# Good_morning.net
KiCad netlist of a schematic drawn in EAGLE
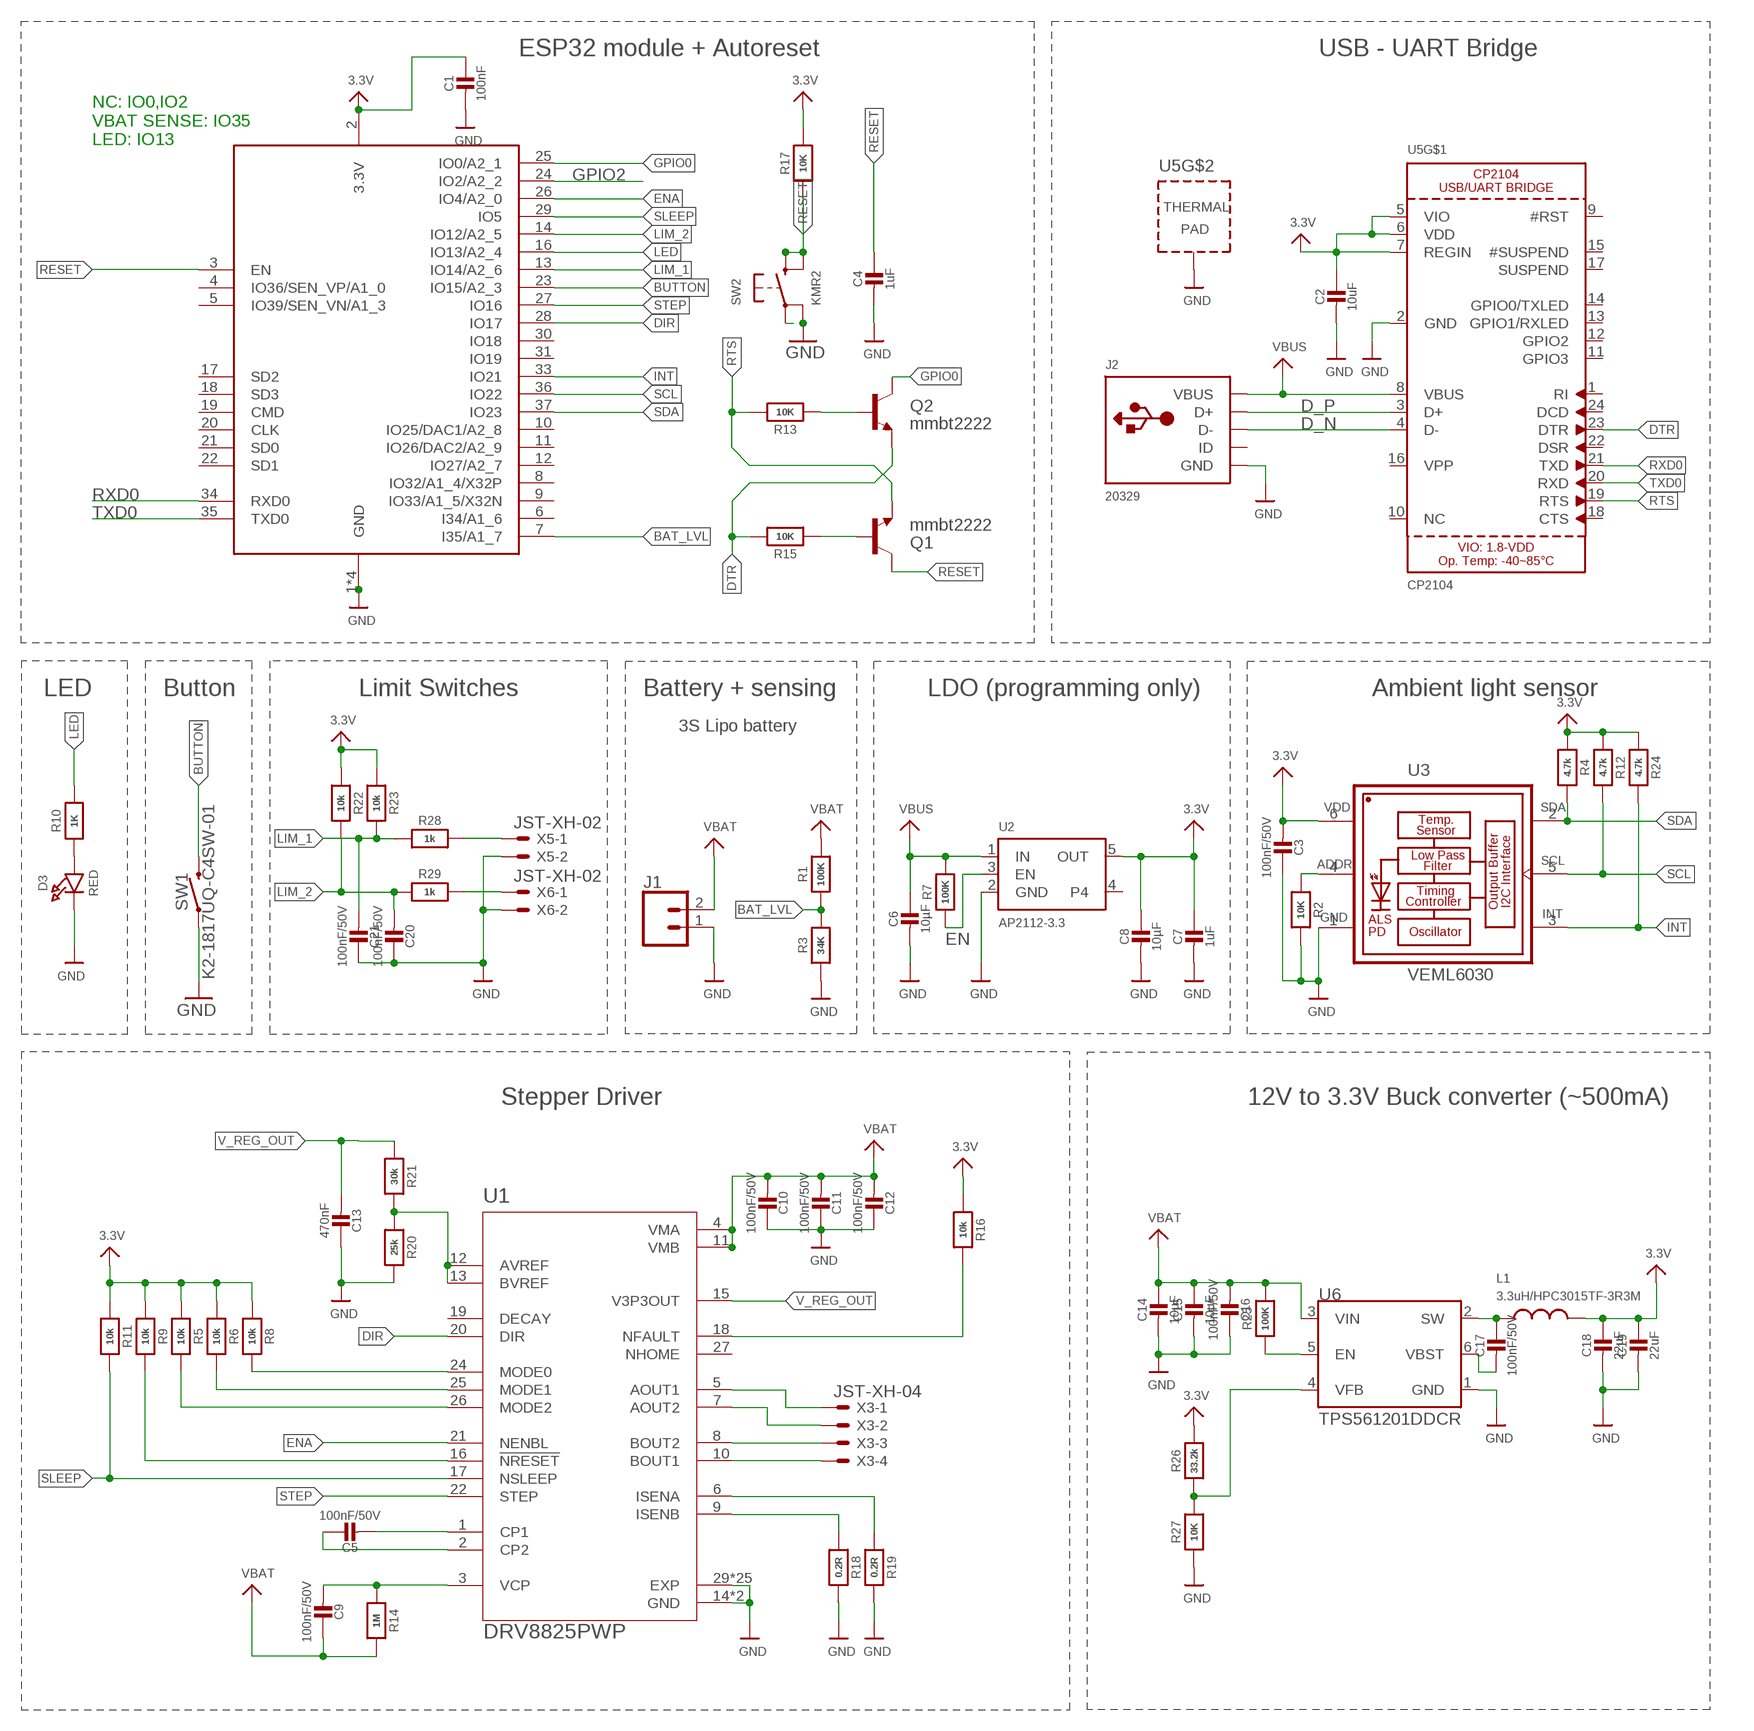
[diagram p0: schematic, sheet 1]

(export (version "E")
  (design (tool "Eeschema 10.0.6"))
  (components
    (comp (ref "C1")
      (value "100nF")
      (footprint "eagle-import:_0402")
      (libsource (lib "eagle-import") (part "CAP_CERAMIC_0402"))
    )
    (comp (ref "C2")
      (value "10uF")
      (footprint "eagle-import:_0402")
      (libsource (lib "eagle-import") (part "CAP_CERAMIC_0402"))
    )
    (comp (ref "C3")
      (value "100nF/50V")
      (footprint "eagle-import:_0402")
      (libsource (lib "eagle-import") (part "CAP_CERAMIC_0402"))
    )
    (comp (ref "C4")
      (value "1uF")
      (footprint "eagle-import:_0402")
      (libsource (lib "eagle-import") (part "CAP_CERAMIC_0402"))
    )
    (comp (ref "C5")
      (value "100nF/50V")
      (footprint "eagle-import:_0805")
      (libsource (lib "eagle-import") (part "CAP_CERAMIC_0805"))
    )
    (comp (ref "C6")
      (value "10µF")
      (footprint "eagle-import:_0402")
      (libsource (lib "eagle-import") (part "CAP_CERAMIC_0402"))
    )
    (comp (ref "C7")
      (value "1uF")
      (footprint "eagle-import:_0402")
      (libsource (lib "eagle-import") (part "CAP_CERAMIC_0402"))
    )
    (comp (ref "C8")
      (value "10µF")
      (footprint "eagle-import:_0402")
      (libsource (lib "eagle-import") (part "CAP_CERAMIC_0402"))
    )
    (comp (ref "C9")
      (value "100nF/50V")
      (footprint "eagle-import:_0805")
      (libsource (lib "eagle-import") (part "CAP_CERAMIC_0805"))
    )
    (comp (ref "C10")
      (value "100nF/50V")
      (footprint "eagle-import:_0805")
      (libsource (lib "eagle-import") (part "CAP_CERAMIC_0805"))
    )
    (comp (ref "C11")
      (value "100nF/50V")
      (footprint "eagle-import:_0805")
      (libsource (lib "eagle-import") (part "CAP_CERAMIC_0805"))
    )
    (comp (ref "C12")
      (value "100nF/50V")
      (footprint "eagle-import:_0805")
      (libsource (lib "eagle-import") (part "CAP_CERAMIC_0805"))
    )
    (comp (ref "C13")
      (value "470nF")
      (footprint "eagle-import:_0402")
      (libsource (lib "eagle-import") (part "CAP_CERAMIC_0402"))
    )
    (comp (ref "C14")
      (value "10µF")
      (footprint "eagle-import:_0402")
      (libsource (lib "eagle-import") (part "CAP_CERAMIC_0402"))
    )
    (comp (ref "C15")
      (value "10µF")
      (footprint "eagle-import:_0402")
      (libsource (lib "eagle-import") (part "CAP_CERAMIC_0402"))
    )
    (comp (ref "C16")
      (value "100nF/50V")
      (footprint "eagle-import:_0402")
      (libsource (lib "eagle-import") (part "CAP_CERAMIC_0402"))
    )
    (comp (ref "C17")
      (value "100nF/50V")
      (footprint "eagle-import:_0402")
      (libsource (lib "eagle-import") (part "CAP_CERAMIC_0402"))
    )
    (comp (ref "C18")
      (value "22uF")
      (footprint "eagle-import:_0402")
      (libsource (lib "eagle-import") (part "CAP_CERAMIC_0402"))
    )
    (comp (ref "C19")
      (value "22uF")
      (footprint "eagle-import:_0402")
      (libsource (lib "eagle-import") (part "CAP_CERAMIC_0402"))
    )
    (comp (ref "C20")
      (value "100nF/50V")
      (footprint "eagle-import:_0402")
      (libsource (lib "eagle-import") (part "CAP_CERAMIC_0402"))
    )
    (comp (ref "C21")
      (value "100nF/50V")
      (footprint "eagle-import:_0402")
      (libsource (lib "eagle-import") (part "CAP_CERAMIC_0402"))
    )
    (comp (ref "D3")
      (value "RED")
      (footprint "eagle-import:CHIPLED_0805_NOOUTLINE")
      (libsource (lib "eagle-import") (part "LED0805_NOOUTLINE"))
    )
    (comp (ref "J1")
      (value "CONN_023.5MM_LOCK")
      (footprint "eagle-import:SCREWTERMINAL-3.5MM-2_LOCK")
      (libsource (lib "eagle-import") (part "CONN_023.5MM_LOCK"))
    )
    (comp (ref "J2")
      (value "20329")
      (footprint "eagle-import:4UCONN_20329_V2")
      (libsource (lib "eagle-import") (part "USB_MICRO_20329_V2"))
    )
    (comp (ref "L1")
      (value "3.3uH/HPC3015TF-3R3M")
      (footprint "eagle-import:WPN4020H100MT")
      (libsource (lib "eagle-import") (part "WPN4020H100MT"))
    )
    (comp (ref "Q1")
      (value "mmbt2222")
      (footprint "eagle-import:SOT23-3")
      (libsource (lib "eagle-import") (part "TRANSISTOR_NPNSOT23-3"))
    )
    (comp (ref "Q2")
      (value "mmbt2222")
      (footprint "eagle-import:SOT23-3")
      (libsource (lib "eagle-import") (part "TRANSISTOR_NPNSOT23-3"))
    )
    (comp (ref "R1")
      (value "100K")
      (footprint "eagle-import:_0402")
      (libsource (lib "eagle-import") (part "RESISTOR_0402"))
    )
    (comp (ref "R2")
      (value "10K")
      (footprint "eagle-import:_0402")
      (libsource (lib "eagle-import") (part "RESISTOR_0402"))
    )
    (comp (ref "R3")
      (value "34K")
      (footprint "eagle-import:_0402")
      (libsource (lib "eagle-import") (part "RESISTOR_0402"))
    )
    (comp (ref "R4")
      (value "4.7k")
      (footprint "eagle-import:_0402")
      (libsource (lib "eagle-import") (part "RESISTOR_0402"))
    )
    (comp (ref "R5")
      (value "10k")
      (footprint "eagle-import:_0402")
      (libsource (lib "eagle-import") (part "RESISTOR_0402"))
    )
    (comp (ref "R6")
      (value "10k")
      (footprint "eagle-import:_0402")
      (libsource (lib "eagle-import") (part "RESISTOR_0402"))
    )
    (comp (ref "R7")
      (value "100K")
      (footprint "eagle-import:_0402")
      (libsource (lib "eagle-import") (part "RESISTOR_0402"))
    )
    (comp (ref "R8")
      (value "10k")
      (footprint "eagle-import:_0402")
      (libsource (lib "eagle-import") (part "RESISTOR_0402"))
    )
    (comp (ref "R9")
      (value "10k")
      (footprint "eagle-import:_0402")
      (libsource (lib "eagle-import") (part "RESISTOR_0402"))
    )
    (comp (ref "R10")
      (value "1K")
      (footprint "eagle-import:_0402")
      (libsource (lib "eagle-import") (part "RESISTOR_0402"))
    )
    (comp (ref "R11")
      (value "10k")
      (footprint "eagle-import:_0402")
      (libsource (lib "eagle-import") (part "RESISTOR_0402"))
    )
    (comp (ref "R12")
      (value "4.7k")
      (footprint "eagle-import:_0402")
      (libsource (lib "eagle-import") (part "RESISTOR_0402"))
    )
    (comp (ref "R13")
      (value "10K")
      (footprint "eagle-import:_0402")
      (libsource (lib "eagle-import") (part "RESISTOR_0402"))
    )
    (comp (ref "R14")
      (value "1M")
      (footprint "eagle-import:_0402")
      (libsource (lib "eagle-import") (part "RESISTOR_0402"))
    )
    (comp (ref "R15")
      (value "10K")
      (footprint "eagle-import:_0402")
      (libsource (lib "eagle-import") (part "RESISTOR_0402"))
    )
    (comp (ref "R16")
      (value "10k")
      (footprint "eagle-import:_0402")
      (libsource (lib "eagle-import") (part "RESISTOR_0402"))
    )
    (comp (ref "R17")
      (value "10K")
      (footprint "eagle-import:_0402")
      (libsource (lib "eagle-import") (part "RESISTOR_0402"))
    )
    (comp (ref "R18")
      (value "0.2R")
      (footprint "eagle-import:_1206")
      (libsource (lib "eagle-import") (part "RESISTOR_1206"))
    )
    (comp (ref "R19")
      (value "0.2R")
      (footprint "eagle-import:_1206")
      (libsource (lib "eagle-import") (part "RESISTOR_1206"))
    )
    (comp (ref "R20")
      (value "25k")
      (footprint "eagle-import:_0402")
      (libsource (lib "eagle-import") (part "RESISTOR_0402"))
    )
    (comp (ref "R21")
      (value "30k")
      (footprint "eagle-import:_0402")
      (libsource (lib "eagle-import") (part "RESISTOR_0402"))
    )
    (comp (ref "R22")
      (value "10k")
      (footprint "eagle-import:_0402")
      (libsource (lib "eagle-import") (part "RESISTOR_0402"))
    )
    (comp (ref "R23")
      (value "10k")
      (footprint "eagle-import:_0402")
      (libsource (lib "eagle-import") (part "RESISTOR_0402"))
    )
    (comp (ref "R24")
      (value "4.7k")
      (footprint "eagle-import:_0402")
      (libsource (lib "eagle-import") (part "RESISTOR_0402"))
    )
    (comp (ref "R25")
      (value "100K")
      (footprint "eagle-import:_0402")
      (libsource (lib "eagle-import") (part "RESISTOR_0402"))
    )
    (comp (ref "R26")
      (value "33.2k")
      (footprint "eagle-import:_0402")
      (libsource (lib "eagle-import") (part "RESISTOR_0402"))
    )
    (comp (ref "R27")
      (value "10K")
      (footprint "eagle-import:_0402")
      (libsource (lib "eagle-import") (part "RESISTOR_0402"))
    )
    (comp (ref "R28")
      (value "1k")
      (footprint "eagle-import:_0402")
      (libsource (lib "eagle-import") (part "RESISTOR_0402"))
    )
    (comp (ref "R29")
      (value "1k")
      (footprint "eagle-import:_0402")
      (libsource (lib "eagle-import") (part "RESISTOR_0402"))
    )
    (comp (ref "SW1")
      (value "K2-1817UQ-C4SW-01")
      (footprint "eagle-import:K2-1817UQ-C4SW-01")
      (libsource (lib "eagle-import") (part "K2-1817UQ-C4SW-01"))
    )
    (comp (ref "SW2")
      (value "KMR2")
      (footprint "eagle-import:BTN_KMR2_4.6X2.8")
      (libsource (lib "eagle-import") (part "SWITCH_TACT_SMT4.6X2.8"))
    )
    (comp (ref "U1")
      (value "DRV8825PWP")
      (footprint "eagle-import:SOP65P640X120-29N")
      (fields (field (name "MF") "Texas Instruments"))
      (libsource (lib "eagle-import") (part "DRV8825PWP"))
    )
    (comp (ref "U2")
      (value "AP2112-3.3")
      (footprint "eagle-import:SOT23-5")
      (libsource (lib "eagle-import") (part "VREG_SOT23-5"))
    )
    (comp (ref "U3")
      (value "VEML6030")
      (footprint "eagle-import:VISHAY_VEML6030_2X2X0.87")
      (fields (field (name "MF") "Vishay"))
      (libsource (lib "eagle-import") (part "VEML6030"))
    )
    (comp (ref "U4")
      (value "ESP32_WROOM32_SKINNY")
      (footprint "eagle-import:WROOM32_SKINNY")
      (libsource (lib "eagle-import") (part "ESP32_WROOM32_SKINNY"))
    )
    (comp (ref "U5")
      (value "CP2104")
      (footprint "eagle-import:QFN24_4MM_SMSC")
      (libsource (lib "eagle-import") (part "CP2104"))
    )
    (comp (ref "U6")
      (value "TPS561201DDCR")
      (footprint "eagle-import:SOT95P280X110-6N")
      (fields (field (name "MF") "Texas Instruments"))
      (libsource (lib "eagle-import") (part "TPS561201DDCR"))
    )
    (comp (ref "X3")
      (value "JST-XH-04")
      (footprint "eagle-import:JST-XH-04-PACKAGE-ROUND-PAD")
      (libsource (lib "eagle-import") (part "JST-XH-04-PIN-ROUND-PAD"))
    )
    (comp (ref "X5")
      (value "JST-XH-02")
      (footprint "eagle-import:JST-XH-02-PACKAGE-ROUND-PAD")
      (libsource (lib "eagle-import") (part "JST-XH-02-PIN-ROUND-PAD"))
    )
    (comp (ref "X6")
      (value "JST-XH-02")
      (footprint "eagle-import:JST-XH-02-PACKAGE-ROUND-PAD")
      (libsource (lib "eagle-import") (part "JST-XH-02-PIN-ROUND-PAD"))
    )
  )
  (nets
    (net (code "1") (name "/D_N") (class "Default")
      (node (ref "J2") (pin "D-") (pinfunction "D-_D-") (pintype "bidirectional"))
      (node (ref "U5") (pin "4") (pinfunction "D-_4") (pintype "bidirectional"))
    )
    (net (code "2") (name "/D_P") (class "Default")
      (node (ref "J2") (pin "D+") (pinfunction "D+_D+") (pintype "bidirectional"))
      (node (ref "U5") (pin "3") (pinfunction "D+_3") (pintype "bidirectional"))
    )
    (net (code "3") (name "/EN") (class "Default")
      (node (ref "R7") (pin "1") (pinfunction "1_1") (pintype "passive"))
      (node (ref "U2") (pin "3") (pinfunction "EN_3") (pintype "input"))
    )
    (net (code "4") (name "/GPIO2") (class "Default")
      (node (ref "U4") (pin "24") (pinfunction "IO2/A2_2_24") (pintype "bidirectional"))
    )
    (net (code "5") (name "3.3V") (class "Default")
      (node (ref "C1") (pin "1") (pinfunction "1_1") (pintype "passive"))
      (node (ref "C18") (pin "1") (pinfunction "1_1") (pintype "passive"))
      (node (ref "C19") (pin "1") (pinfunction "1_1") (pintype "passive"))
      (node (ref "C2") (pin "1") (pinfunction "1_1") (pintype "passive"))
      (node (ref "C3") (pin "2") (pinfunction "2_2") (pintype "passive"))
      (node (ref "C7") (pin "1") (pinfunction "1_1") (pintype "passive"))
      (node (ref "C8") (pin "1") (pinfunction "1_1") (pintype "passive"))
      (node (ref "L1") (pin "2") (pinfunction "2_2") (pintype "passive"))
      (node (ref "R11") (pin "1") (pinfunction "1_1") (pintype "passive"))
      (node (ref "R12") (pin "1") (pinfunction "1_1") (pintype "passive"))
      (node (ref "R16") (pin "1") (pinfunction "1_1") (pintype "passive"))
      (node (ref "R17") (pin "2") (pinfunction "2_2") (pintype "passive"))
      (node (ref "R22") (pin "1") (pinfunction "1_1") (pintype "passive"))
      (node (ref "R23") (pin "1") (pinfunction "1_1") (pintype "passive"))
      (node (ref "R24") (pin "1") (pinfunction "1_1") (pintype "passive"))
      (node (ref "R26") (pin "1") (pinfunction "1_1") (pintype "passive"))
      (node (ref "R4") (pin "1") (pinfunction "1_1") (pintype "passive"))
      (node (ref "R5") (pin "1") (pinfunction "1_1") (pintype "passive"))
      (node (ref "R6") (pin "1") (pinfunction "1_1") (pintype "passive"))
      (node (ref "R8") (pin "1") (pinfunction "1_1") (pintype "passive"))
      (node (ref "R9") (pin "1") (pinfunction "1_1") (pintype "passive"))
      (node (ref "U2") (pin "5") (pinfunction "OUT_5") (pintype "power_in"))
      (node (ref "U3") (pin "6") (pinfunction "VDD_6") (pintype "power_in"))
      (node (ref "U4") (pin "2") (pinfunction "3.3V_2") (pintype "passive"))
      (node (ref "U5") (pin "5") (pinfunction "VIO_5") (pintype "power_in"))
      (node (ref "U5") (pin "6") (pinfunction "VDD_6") (pintype "power_in"))
      (node (ref "U5") (pin "7") (pinfunction "REGIN_7") (pintype "power_in"))
    )
    (net (code "6") (name "BAT_LVL") (class "Default")
      (node (ref "R1") (pin "1") (pinfunction "1_1") (pintype "passive"))
      (node (ref "R3") (pin "2") (pinfunction "2_2") (pintype "passive"))
      (node (ref "U4") (pin "7") (pinfunction "I35/A1_7_7") (pintype "bidirectional"))
    )
    (net (code "7") (name "BUTTON") (class "Default")
      (node (ref "SW1") (pin "P$2") (pinfunction "2_P$2") (pintype "passive"))
      (node (ref "U4") (pin "23") (pinfunction "IO15/A2_3_23") (pintype "bidirectional"))
    )
    (net (code "8") (name "DIR") (class "Default")
      (node (ref "U1") (pin "20") (pinfunction "DIR_20") (pintype "input"))
      (node (ref "U4") (pin "28") (pinfunction "IO17_28") (pintype "bidirectional"))
    )
    (net (code "9") (name "DTR") (class "Default")
      (node (ref "Q2") (pin "2") (pinfunction "E_2") (pintype "passive"))
      (node (ref "R15") (pin "2") (pinfunction "2_2") (pintype "passive"))
      (node (ref "U5") (pin "23") (pinfunction "DTR_23") (pintype "output"))
    )
    (net (code "10") (name "ENA") (class "Default")
      (node (ref "U1") (pin "21") (pinfunction "NENBL_21") (pintype "input"))
      (node (ref "U4") (pin "26") (pinfunction "IO4/A2_0_26") (pintype "bidirectional"))
    )
    (net (code "11") (name "GND") (class "Default")
      (node (ref "C1") (pin "2") (pinfunction "2_2") (pintype "passive"))
      (node (ref "C10") (pin "1") (pinfunction "1_1") (pintype "passive"))
      (node (ref "C11") (pin "1") (pinfunction "1_1") (pintype "passive"))
      (node (ref "C12") (pin "1") (pinfunction "1_1") (pintype "passive"))
      (node (ref "C13") (pin "1") (pinfunction "1_1") (pintype "passive"))
      (node (ref "C14") (pin "2") (pinfunction "2_2") (pintype "passive"))
      (node (ref "C15") (pin "2") (pinfunction "2_2") (pintype "passive"))
      (node (ref "C16") (pin "1") (pinfunction "1_1") (pintype "passive"))
      (node (ref "C18") (pin "2") (pinfunction "2_2") (pintype "passive"))
      (node (ref "C19") (pin "2") (pinfunction "2_2") (pintype "passive"))
      (node (ref "C2") (pin "2") (pinfunction "2_2") (pintype "passive"))
      (node (ref "C20") (pin "1") (pinfunction "1_1") (pintype "passive"))
      (node (ref "C21") (pin "1") (pinfunction "1_1") (pintype "passive"))
      (node (ref "C3") (pin "1") (pinfunction "1_1") (pintype "passive"))
      (node (ref "C4") (pin "2") (pinfunction "2_2") (pintype "passive"))
      (node (ref "C6") (pin "2") (pinfunction "2_2") (pintype "passive"))
      (node (ref "C7") (pin "2") (pinfunction "2_2") (pintype "passive"))
      (node (ref "C8") (pin "2") (pinfunction "2_2") (pintype "passive"))
      (node (ref "D3") (pin "C") (pinfunction "C_C") (pintype "passive"))
      (node (ref "J1") (pin "1") (pinfunction "1_1") (pintype "passive"))
      (node (ref "J2") (pin "BASE@1") (pinfunction "GND_BASE@1") (pintype "power_in"))
      (node (ref "J2") (pin "BASE@2") (pinfunction "GND_BASE@2") (pintype "power_in"))
      (node (ref "J2") (pin "GND") (pinfunction "GND_GND") (pintype "power_in"))
      (node (ref "J2") (pin "SPRT@1") (pinfunction "GND_SPRT@1") (pintype "power_in"))
      (node (ref "J2") (pin "SPRT@2") (pinfunction "GND_SPRT@2") (pintype "power_in"))
      (node (ref "J2") (pin "SPRT@3") (pinfunction "GND_SPRT@3") (pintype "power_in"))
      (node (ref "J2") (pin "SPRT@4") (pinfunction "GND_SPRT@4") (pintype "power_in"))
      (node (ref "R18") (pin "2") (pinfunction "2_2") (pintype "passive"))
      (node (ref "R19") (pin "2") (pinfunction "2_2") (pintype "passive"))
      (node (ref "R2") (pin "2") (pinfunction "2_2") (pintype "passive"))
      (node (ref "R20") (pin "2") (pinfunction "2_2") (pintype "passive"))
      (node (ref "R27") (pin "1") (pinfunction "1_1") (pintype "passive"))
      (node (ref "R3") (pin "1") (pinfunction "1_1") (pintype "passive"))
      (node (ref "SW1") (pin "P$1") (pinfunction "1_P$1") (pintype "passive"))
      (node (ref "SW2") (pin "A'") (pinfunction "P1_A'") (pintype "passive"))
      (node (ref "U1") (pin "14") (pinfunction "GND_14") (pintype "power_in"))
      (node (ref "U1") (pin "28") (pinfunction "GND_28") (pintype "power_in"))
      (node (ref "U1") (pin "29") (pinfunction "EXP_29") (pintype "power_in"))
      (node (ref "U1") (pin "P1") (pinfunction "EXP_P1") (pintype "power_in"))
      (node (ref "U1") (pin "P10") (pinfunction "EXP_P10") (pintype "power_in"))
      (node (ref "U1") (pin "P11") (pinfunction "EXP_P11") (pintype "power_in"))
      (node (ref "U1") (pin "P12") (pinfunction "EXP_P12") (pintype "power_in"))
      (node (ref "U1") (pin "P13") (pinfunction "EXP_P13") (pintype "power_in"))
      (node (ref "U1") (pin "P14") (pinfunction "EXP_P14") (pintype "power_in"))
      (node (ref "U1") (pin "P15") (pinfunction "EXP_P15") (pintype "power_in"))
      (node (ref "U1") (pin "P16") (pinfunction "EXP_P16") (pintype "power_in"))
      (node (ref "U1") (pin "P17") (pinfunction "EXP_P17") (pintype "power_in"))
      (node (ref "U1") (pin "P18") (pinfunction "EXP_P18") (pintype "power_in"))
      (node (ref "U1") (pin "P19") (pinfunction "EXP_P19") (pintype "power_in"))
      (node (ref "U1") (pin "P2") (pinfunction "EXP_P2") (pintype "power_in"))
      (node (ref "U1") (pin "P20") (pinfunction "EXP_P20") (pintype "power_in"))
      (node (ref "U1") (pin "P21") (pinfunction "EXP_P21") (pintype "power_in"))
      (node (ref "U1") (pin "P22") (pinfunction "EXP_P22") (pintype "power_in"))
      (node (ref "U1") (pin "P23") (pinfunction "EXP_P23") (pintype "power_in"))
      (node (ref "U1") (pin "P24") (pinfunction "EXP_P24") (pintype "power_in"))
      (node (ref "U1") (pin "P3") (pinfunction "EXP_P3") (pintype "power_in"))
      (node (ref "U1") (pin "P4") (pinfunction "EXP_P4") (pintype "power_in"))
      (node (ref "U1") (pin "P5") (pinfunction "EXP_P5") (pintype "power_in"))
      (node (ref "U1") (pin "P6") (pinfunction "EXP_P6") (pintype "power_in"))
      (node (ref "U1") (pin "P7") (pinfunction "EXP_P7") (pintype "power_in"))
      (node (ref "U1") (pin "P8") (pinfunction "EXP_P8") (pintype "power_in"))
      (node (ref "U1") (pin "P9") (pinfunction "EXP_P9") (pintype "power_in"))
      (node (ref "U2") (pin "2") (pinfunction "GND_2") (pintype "power_in"))
      (node (ref "U3") (pin "1") (pinfunction "GND_1") (pintype "power_in"))
      (node (ref "U4") (pin "1") (pinfunction "GND_1") (pintype "passive"))
      (node (ref "U4") (pin "15") (pinfunction "GND_15") (pintype "passive"))
      (node (ref "U4") (pin "38") (pinfunction "GND_38") (pintype "passive"))
      (node (ref "U4") (pin "P$1") (pinfunction "GND_P$1") (pintype "passive"))
      (node (ref "U5") (pin "2") (pinfunction "GND_2") (pintype "power_in"))
      (node (ref "U5") (pin "THERM") (pinfunction "TP_THERM") (pintype "power_in"))
      (node (ref "U6") (pin "1") (pinfunction "GND_1") (pintype "power_in"))
      (node (ref "X5") (pin "2") (pinfunction "S_2") (pintype "passive"))
      (node (ref "X6") (pin "2") (pinfunction "S_2") (pintype "passive"))
    )
    (net (code "12") (name "GPIO0") (class "Default")
      (node (ref "Q2") (pin "3") (pinfunction "C_3") (pintype "passive"))
      (node (ref "U4") (pin "25") (pinfunction "IO0/A2_1_25") (pintype "bidirectional"))
    )
    (net (code "13") (name "INT") (class "Default")
      (node (ref "R24") (pin "2") (pinfunction "2_2") (pintype "passive"))
      (node (ref "U3") (pin "3") (pinfunction "INT_3") (pintype "output"))
      (node (ref "U4") (pin "33") (pinfunction "IO21_33") (pintype "bidirectional"))
    )
    (net (code "14") (name "LED") (class "Default")
      (node (ref "R10") (pin "1") (pinfunction "1_1") (pintype "passive"))
      (node (ref "U4") (pin "16") (pinfunction "IO13/A2_4_16") (pintype "bidirectional"))
    )
    (net (code "15") (name "LIM_1") (class "Default")
      (node (ref "C21") (pin "2") (pinfunction "2_2") (pintype "passive"))
      (node (ref "R23") (pin "2") (pinfunction "2_2") (pintype "passive"))
      (node (ref "R28") (pin "1") (pinfunction "1_1") (pintype "passive"))
      (node (ref "U4") (pin "13") (pinfunction "IO14/A2_6_13") (pintype "bidirectional"))
    )
    (net (code "16") (name "LIM_2") (class "Default")
      (node (ref "C20") (pin "2") (pinfunction "2_2") (pintype "passive"))
      (node (ref "R22") (pin "2") (pinfunction "2_2") (pintype "passive"))
      (node (ref "R29") (pin "1") (pinfunction "1_1") (pintype "passive"))
      (node (ref "U4") (pin "14") (pinfunction "IO12/A2_5_14") (pintype "bidirectional"))
    )
    (net (code "17") (name "Net-(D3-PadA)") (class "Default")
      (node (ref "D3") (pin "A") (pinfunction "A_A") (pintype "passive"))
      (node (ref "R10") (pin "2") (pinfunction "2_2") (pintype "passive"))
    )
    (net (code "18") (name "Net-(Q1-B)") (class "Default")
      (node (ref "Q1") (pin "1") (pinfunction "B_1") (pintype "passive"))
      (node (ref "R15") (pin "1") (pinfunction "1_1") (pintype "passive"))
    )
    (net (code "19") (name "Net-(Q2-B)") (class "Default")
      (node (ref "Q2") (pin "1") (pinfunction "B_1") (pintype "passive"))
      (node (ref "R13") (pin "1") (pinfunction "1_1") (pintype "passive"))
    )
    (net (code "20") (name "Net-(U1-AOUT1)") (class "Default")
      (node (ref "U1") (pin "5") (pinfunction "AOUT1_5") (pintype "output"))
      (node (ref "X3") (pin "1") (pinfunction "S_1") (pintype "passive"))
    )
    (net (code "21") (name "Net-(U1-AOUT2)") (class "Default")
      (node (ref "U1") (pin "7") (pinfunction "AOUT2_7") (pintype "output"))
      (node (ref "X3") (pin "2") (pinfunction "S_2") (pintype "passive"))
    )
    (net (code "22") (name "Net-(U1-AVREF)") (class "Default")
      (node (ref "R20") (pin "1") (pinfunction "1_1") (pintype "passive"))
      (node (ref "R21") (pin "2") (pinfunction "2_2") (pintype "passive"))
      (node (ref "U1") (pin "12") (pinfunction "AVREF_12") (pintype "input"))
      (node (ref "U1") (pin "13") (pinfunction "BVREF_13") (pintype "input"))
    )
    (net (code "23") (name "Net-(U1-BOUT1)") (class "Default")
      (node (ref "U1") (pin "10") (pinfunction "BOUT1_10") (pintype "output"))
      (node (ref "X3") (pin "4") (pinfunction "S_4") (pintype "passive"))
    )
    (net (code "24") (name "Net-(U1-BOUT2)") (class "Default")
      (node (ref "U1") (pin "8") (pinfunction "BOUT2_8") (pintype "output"))
      (node (ref "X3") (pin "3") (pinfunction "S_3") (pintype "passive"))
    )
    (net (code "25") (name "Net-(U1-CP1)") (class "Default")
      (node (ref "C5") (pin "2") (pinfunction "2_2") (pintype "passive"))
      (node (ref "U1") (pin "1") (pinfunction "CP1_1") (pintype "bidirectional"))
    )
    (net (code "26") (name "Net-(U1-CP2)") (class "Default")
      (node (ref "C5") (pin "1") (pinfunction "1_1") (pintype "passive"))
      (node (ref "U1") (pin "2") (pinfunction "CP2_2") (pintype "bidirectional"))
    )
    (net (code "27") (name "Net-(U1-ISENA)") (class "Default")
      (node (ref "R19") (pin "1") (pinfunction "1_1") (pintype "passive"))
      (node (ref "U1") (pin "6") (pinfunction "ISENA_6") (pintype "bidirectional"))
    )
    (net (code "28") (name "Net-(U1-ISENB)") (class "Default")
      (node (ref "R18") (pin "1") (pinfunction "1_1") (pintype "passive"))
      (node (ref "U1") (pin "9") (pinfunction "ISENB_9") (pintype "bidirectional"))
    )
    (net (code "29") (name "Net-(U1-MODE0)") (class "Default")
      (node (ref "R8") (pin "2") (pinfunction "2_2") (pintype "passive"))
      (node (ref "U1") (pin "24") (pinfunction "MODE0_24") (pintype "input"))
    )
    (net (code "30") (name "Net-(U1-MODE1)") (class "Default")
      (node (ref "R6") (pin "2") (pinfunction "2_2") (pintype "passive"))
      (node (ref "U1") (pin "25") (pinfunction "MODE1_25") (pintype "input"))
    )
    (net (code "31") (name "Net-(U1-MODE2)") (class "Default")
      (node (ref "R5") (pin "2") (pinfunction "2_2") (pintype "passive"))
      (node (ref "U1") (pin "26") (pinfunction "MODE2_26") (pintype "input"))
    )
    (net (code "32") (name "Net-(U1-NFAULT)") (class "Default")
      (node (ref "R16") (pin "2") (pinfunction "2_2") (pintype "passive"))
      (node (ref "U1") (pin "18") (pinfunction "NFAULT_18") (pintype "output"))
    )
    (net (code "33") (name "Net-(U1-VCP)") (class "Default")
      (node (ref "C9") (pin "2") (pinfunction "2_2") (pintype "passive"))
      (node (ref "R14") (pin "1") (pinfunction "1_1") (pintype "passive"))
      (node (ref "U1") (pin "3") (pinfunction "VCP_3") (pintype "bidirectional"))
    )
    (net (code "34") (name "Net-(U1-~{NRESET})") (class "Default")
      (node (ref "R9") (pin "2") (pinfunction "2_2") (pintype "passive"))
      (node (ref "U1") (pin "16") (pinfunction "~{NRESET}_16") (pintype "input"))
    )
    (net (code "35") (name "Net-(U3-ADDR)") (class "Default")
      (node (ref "R2") (pin "1") (pinfunction "1_1") (pintype "passive"))
      (node (ref "U3") (pin "4") (pinfunction "ADDR_4") (pintype "bidirectional"))
    )
    (net (code "36") (name "Net-(U6-EN)") (class "Default")
      (node (ref "R25") (pin "1") (pinfunction "1_1") (pintype "passive"))
      (node (ref "U6") (pin "5") (pinfunction "EN_5") (pintype "input"))
    )
    (net (code "37") (name "Net-(U6-SW)") (class "Default")
      (node (ref "C17") (pin "1") (pinfunction "1_1") (pintype "passive"))
      (node (ref "L1") (pin "1") (pinfunction "1_1") (pintype "passive"))
      (node (ref "U6") (pin "2") (pinfunction "SW_2") (pintype "output"))
    )
    (net (code "38") (name "Net-(U6-VBST)") (class "Default")
      (node (ref "C17") (pin "2") (pinfunction "2_2") (pintype "passive"))
      (node (ref "U6") (pin "6") (pinfunction "VBST_6") (pintype "passive"))
    )
    (net (code "39") (name "Net-(U6-VFB)") (class "Default")
      (node (ref "R26") (pin "2") (pinfunction "2_2") (pintype "passive"))
      (node (ref "R27") (pin "2") (pinfunction "2_2") (pintype "passive"))
      (node (ref "U6") (pin "4") (pinfunction "VFB_4") (pintype "input"))
    )
    (net (code "40") (name "Net-(X5A-S)") (class "Default")
      (node (ref "R28") (pin "2") (pinfunction "2_2") (pintype "passive"))
      (node (ref "X5") (pin "1") (pinfunction "S_1") (pintype "passive"))
    )
    (net (code "41") (name "Net-(X6A-S)") (class "Default")
      (node (ref "R29") (pin "2") (pinfunction "2_2") (pintype "passive"))
      (node (ref "X6") (pin "1") (pinfunction "S_1") (pintype "passive"))
    )
    (net (code "42") (name "RESET") (class "Default")
      (node (ref "C4") (pin "1") (pinfunction "1_1") (pintype "passive"))
      (node (ref "Q1") (pin "3") (pinfunction "C_3") (pintype "passive"))
      (node (ref "R17") (pin "1") (pinfunction "1_1") (pintype "passive"))
      (node (ref "SW2") (pin "B") (pinfunction "S_B") (pintype "passive"))
      (node (ref "SW2") (pin "B'") (pinfunction "S1_B'") (pintype "passive"))
      (node (ref "U4") (pin "3") (pinfunction "EN_3") (pintype "input"))
    )
    (net (code "43") (name "RTS") (class "Default")
      (node (ref "Q1") (pin "2") (pinfunction "E_2") (pintype "passive"))
      (node (ref "R13") (pin "2") (pinfunction "2_2") (pintype "passive"))
      (node (ref "U5") (pin "19") (pinfunction "RTS_19") (pintype "output"))
    )
    (net (code "44") (name "RXD0") (class "Default")
      (node (ref "U4") (pin "34") (pinfunction "RXD0_34") (pintype "input"))
      (node (ref "U5") (pin "21") (pinfunction "TXD_21") (pintype "output"))
    )
    (net (code "45") (name "SCL") (class "Default")
      (node (ref "R12") (pin "2") (pinfunction "2_2") (pintype "passive"))
      (node (ref "U3") (pin "5") (pinfunction "SCL_5") (pintype "input"))
      (node (ref "U4") (pin "36") (pinfunction "IO22_36") (pintype "bidirectional"))
    )
    (net (code "46") (name "SDA") (class "Default")
      (node (ref "R4") (pin "2") (pinfunction "2_2") (pintype "passive"))
      (node (ref "U3") (pin "2") (pinfunction "SDA_2") (pintype "bidirectional"))
      (node (ref "U4") (pin "37") (pinfunction "IO23_37") (pintype "bidirectional"))
    )
    (net (code "47") (name "SLEEP") (class "Default")
      (node (ref "R11") (pin "2") (pinfunction "2_2") (pintype "passive"))
      (node (ref "U1") (pin "17") (pinfunction "NSLEEP_17") (pintype "input"))
      (node (ref "U4") (pin "29") (pinfunction "IO5_29") (pintype "bidirectional"))
    )
    (net (code "48") (name "STEP") (class "Default")
      (node (ref "U1") (pin "22") (pinfunction "STEP_22") (pintype "input"))
      (node (ref "U4") (pin "27") (pinfunction "IO16_27") (pintype "bidirectional"))
    )
    (net (code "49") (name "TXD0") (class "Default")
      (node (ref "U4") (pin "35") (pinfunction "TXD0_35") (pintype "output"))
      (node (ref "U5") (pin "20") (pinfunction "RXD_20") (pintype "input"))
    )
    (net (code "50") (name "VBAT") (class "Default")
      (node (ref "C10") (pin "2") (pinfunction "2_2") (pintype "passive"))
      (node (ref "C11") (pin "2") (pinfunction "2_2") (pintype "passive"))
      (node (ref "C12") (pin "2") (pinfunction "2_2") (pintype "passive"))
      (node (ref "C14") (pin "1") (pinfunction "1_1") (pintype "passive"))
      (node (ref "C15") (pin "1") (pinfunction "1_1") (pintype "passive"))
      (node (ref "C16") (pin "2") (pinfunction "2_2") (pintype "passive"))
      (node (ref "C9") (pin "1") (pinfunction "1_1") (pintype "passive"))
      (node (ref "J1") (pin "2") (pinfunction "2_2") (pintype "passive"))
      (node (ref "R1") (pin "2") (pinfunction "2_2") (pintype "passive"))
      (node (ref "R14") (pin "2") (pinfunction "2_2") (pintype "passive"))
      (node (ref "R25") (pin "2") (pinfunction "2_2") (pintype "passive"))
      (node (ref "U1") (pin "11") (pinfunction "VMB_11") (pintype "power_in"))
      (node (ref "U1") (pin "4") (pinfunction "VMA_4") (pintype "power_in"))
      (node (ref "U6") (pin "3") (pinfunction "VIN_3") (pintype "input"))
    )
    (net (code "51") (name "VBUS") (class "Default")
      (node (ref "C6") (pin "1") (pinfunction "1_1") (pintype "passive"))
      (node (ref "J2") (pin "VBUS") (pinfunction "VBUS_VBUS") (pintype "power_in"))
      (node (ref "R7") (pin "2") (pinfunction "2_2") (pintype "passive"))
      (node (ref "U2") (pin "1") (pinfunction "IN_1") (pintype "power_in"))
      (node (ref "U5") (pin "8") (pinfunction "VBUS_8") (pintype "power_in"))
    )
    (net (code "52") (name "V_REG_OUT") (class "Default")
      (node (ref "C13") (pin "2") (pinfunction "2_2") (pintype "passive"))
      (node (ref "R21") (pin "1") (pinfunction "1_1") (pintype "passive"))
      (node (ref "U1") (pin "15") (pinfunction "V3P3OUT_15") (pintype "output"))
    )
    (net (code "53") (name "unconnected-(J2-PadID)") (class "Default")
      (node (ref "J2") (pin "ID") (pinfunction "ID_ID") (pintype "bidirectional"))
    )
    (net (code "54") (name "unconnected-(SW2-P-PadA)") (class "Default")
      (node (ref "SW2") (pin "A") (pinfunction "P_A") (pintype "passive"))
    )
    (net (code "55") (name "unconnected-(U1-DECAY-Pad19)") (class "Default")
      (node (ref "U1") (pin "19") (pinfunction "DECAY_19") (pintype "input"))
    )
    (net (code "56") (name "unconnected-(U1-NHOME-Pad27)") (class "Default")
      (node (ref "U1") (pin "27") (pinfunction "NHOME_27") (pintype "output"))
    )
    (net (code "57") (name "unconnected-(U2-P4-Pad4)") (class "Default")
      (node (ref "U2") (pin "4") (pinfunction "P4_4") (pintype "bidirectional"))
    )
    (net (code "58") (name "unconnected-(U4-CLK-Pad20)") (class "Default")
      (node (ref "U4") (pin "20") (pinfunction "CLK_20") (pintype "bidirectional"))
    )
    (net (code "59") (name "unconnected-(U4-CMD-Pad19)") (class "Default")
      (node (ref "U4") (pin "19") (pinfunction "CMD_19") (pintype "bidirectional"))
    )
    (net (code "60") (name "unconnected-(U4-I34{slash}A1_6-Pad6)") (class "Default")
      (node (ref "U4") (pin "6") (pinfunction "I34/A1_6_6") (pintype "bidirectional"))
    )
    (net (code "61") (name "unconnected-(U4-IO18-Pad30)") (class "Default")
      (node (ref "U4") (pin "30") (pinfunction "IO18_30") (pintype "bidirectional"))
    )
    (net (code "62") (name "unconnected-(U4-IO19-Pad31)") (class "Default")
      (node (ref "U4") (pin "31") (pinfunction "IO19_31") (pintype "bidirectional"))
    )
    (net (code "63") (name "unconnected-(U4-IO25{slash}DAC1{slash}A2_8-Pad10)") (class "Default")
      (node (ref "U4") (pin "10") (pinfunction "IO25/DAC1/A2_8_10") (pintype "bidirectional"))
    )
    (net (code "64") (name "unconnected-(U4-IO26{slash}DAC2{slash}A2_9-Pad11)") (class "Default")
      (node (ref "U4") (pin "11") (pinfunction "IO26/DAC2/A2_9_11") (pintype "bidirectional"))
    )
    (net (code "65") (name "unconnected-(U4-IO27{slash}A2_7-Pad12)") (class "Default")
      (node (ref "U4") (pin "12") (pinfunction "IO27/A2_7_12") (pintype "bidirectional"))
    )
    (net (code "66") (name "unconnected-(U4-IO32{slash}A1_4{slash}X32P-Pad8)") (class "Default")
      (node (ref "U4") (pin "8") (pinfunction "IO32/A1_4/X32P_8") (pintype "bidirectional"))
    )
    (net (code "67") (name "unconnected-(U4-IO33{slash}A1_5{slash}X32N-Pad9)") (class "Default")
      (node (ref "U4") (pin "9") (pinfunction "IO33/A1_5/X32N_9") (pintype "bidirectional"))
    )
    (net (code "68") (name "unconnected-(U4-IO36{slash}SEN_VP{slash}A1_0-Pad4)") (class "Default")
      (node (ref "U4") (pin "4") (pinfunction "IO36/SEN_VP/A1_0_4") (pintype "passive"))
    )
    (net (code "69") (name "unconnected-(U4-IO39{slash}SEN_VN{slash}A1_3-Pad5)") (class "Default")
      (node (ref "U4") (pin "5") (pinfunction "IO39/SEN_VN/A1_3_5") (pintype "passive"))
    )
    (net (code "70") (name "unconnected-(U4-SD0-Pad21)") (class "Default")
      (node (ref "U4") (pin "21") (pinfunction "SD0_21") (pintype "bidirectional"))
    )
    (net (code "71") (name "unconnected-(U4-SD1-Pad22)") (class "Default")
      (node (ref "U4") (pin "22") (pinfunction "SD1_22") (pintype "bidirectional"))
    )
    (net (code "72") (name "unconnected-(U4-SD2-Pad17)") (class "Default")
      (node (ref "U4") (pin "17") (pinfunction "SD2_17") (pintype "bidirectional"))
    )
    (net (code "73") (name "unconnected-(U4-SD3-Pad18)") (class "Default")
      (node (ref "U4") (pin "18") (pinfunction "SD3_18") (pintype "bidirectional"))
    )
    (net (code "74") (name "unconnected-(U5A-#RST-Pad9)") (class "Default")
      (node (ref "U5") (pin "9") (pinfunction "#RST_9") (pintype "bidirectional"))
    )
    (net (code "75") (name "unconnected-(U5A-#SUSPEND-Pad15)") (class "Default")
      (node (ref "U5") (pin "15") (pinfunction "#SUSPEND_15") (pintype "output"))
    )
    (net (code "76") (name "unconnected-(U5A-CTS-Pad18)") (class "Default")
      (node (ref "U5") (pin "18") (pinfunction "CTS_18") (pintype "input"))
    )
    (net (code "77") (name "unconnected-(U5A-DCD-Pad24)") (class "Default")
      (node (ref "U5") (pin "24") (pinfunction "DCD_24") (pintype "input"))
    )
    (net (code "78") (name "unconnected-(U5A-DSR-Pad22)") (class "Default")
      (node (ref "U5") (pin "22") (pinfunction "DSR_22") (pintype "input"))
    )
    (net (code "79") (name "unconnected-(U5A-GPIO0{slash}TXLED-Pad14)") (class "Default")
      (node (ref "U5") (pin "14") (pinfunction "GPIO0/TXLED_14") (pintype "bidirectional"))
    )
    (net (code "80") (name "unconnected-(U5A-GPIO1{slash}RXLED-Pad13)") (class "Default")
      (node (ref "U5") (pin "13") (pinfunction "GPIO1/RXLED_13") (pintype "bidirectional"))
    )
    (net (code "81") (name "unconnected-(U5A-GPIO2-Pad12)") (class "Default")
      (node (ref "U5") (pin "12") (pinfunction "GPIO2_12") (pintype "bidirectional"))
    )
    (net (code "82") (name "unconnected-(U5A-GPIO3-Pad11)") (class "Default")
      (node (ref "U5") (pin "11") (pinfunction "GPIO3_11") (pintype "bidirectional"))
    )
    (net (code "83") (name "unconnected-(U5A-NC-Pad10)") (class "Default")
      (node (ref "U5") (pin "10") (pinfunction "NC_10") (pintype "no_connect"))
    )
    (net (code "84") (name "unconnected-(U5A-RI-Pad1)") (class "Default")
      (node (ref "U5") (pin "1") (pinfunction "RI_1") (pintype "input"))
    )
    (net (code "85") (name "unconnected-(U5A-SUSPEND-Pad17)") (class "Default")
      (node (ref "U5") (pin "17") (pinfunction "SUSPEND_17") (pintype "output"))
    )
    (net (code "86") (name "unconnected-(U5A-VPP-Pad16)") (class "Default")
      (node (ref "U5") (pin "16") (pinfunction "VPP_16") (pintype "bidirectional"))
    )
  )
)
